# drawbars_v12_2019.net
KiCad netlist of a schematic drawn in EAGLE
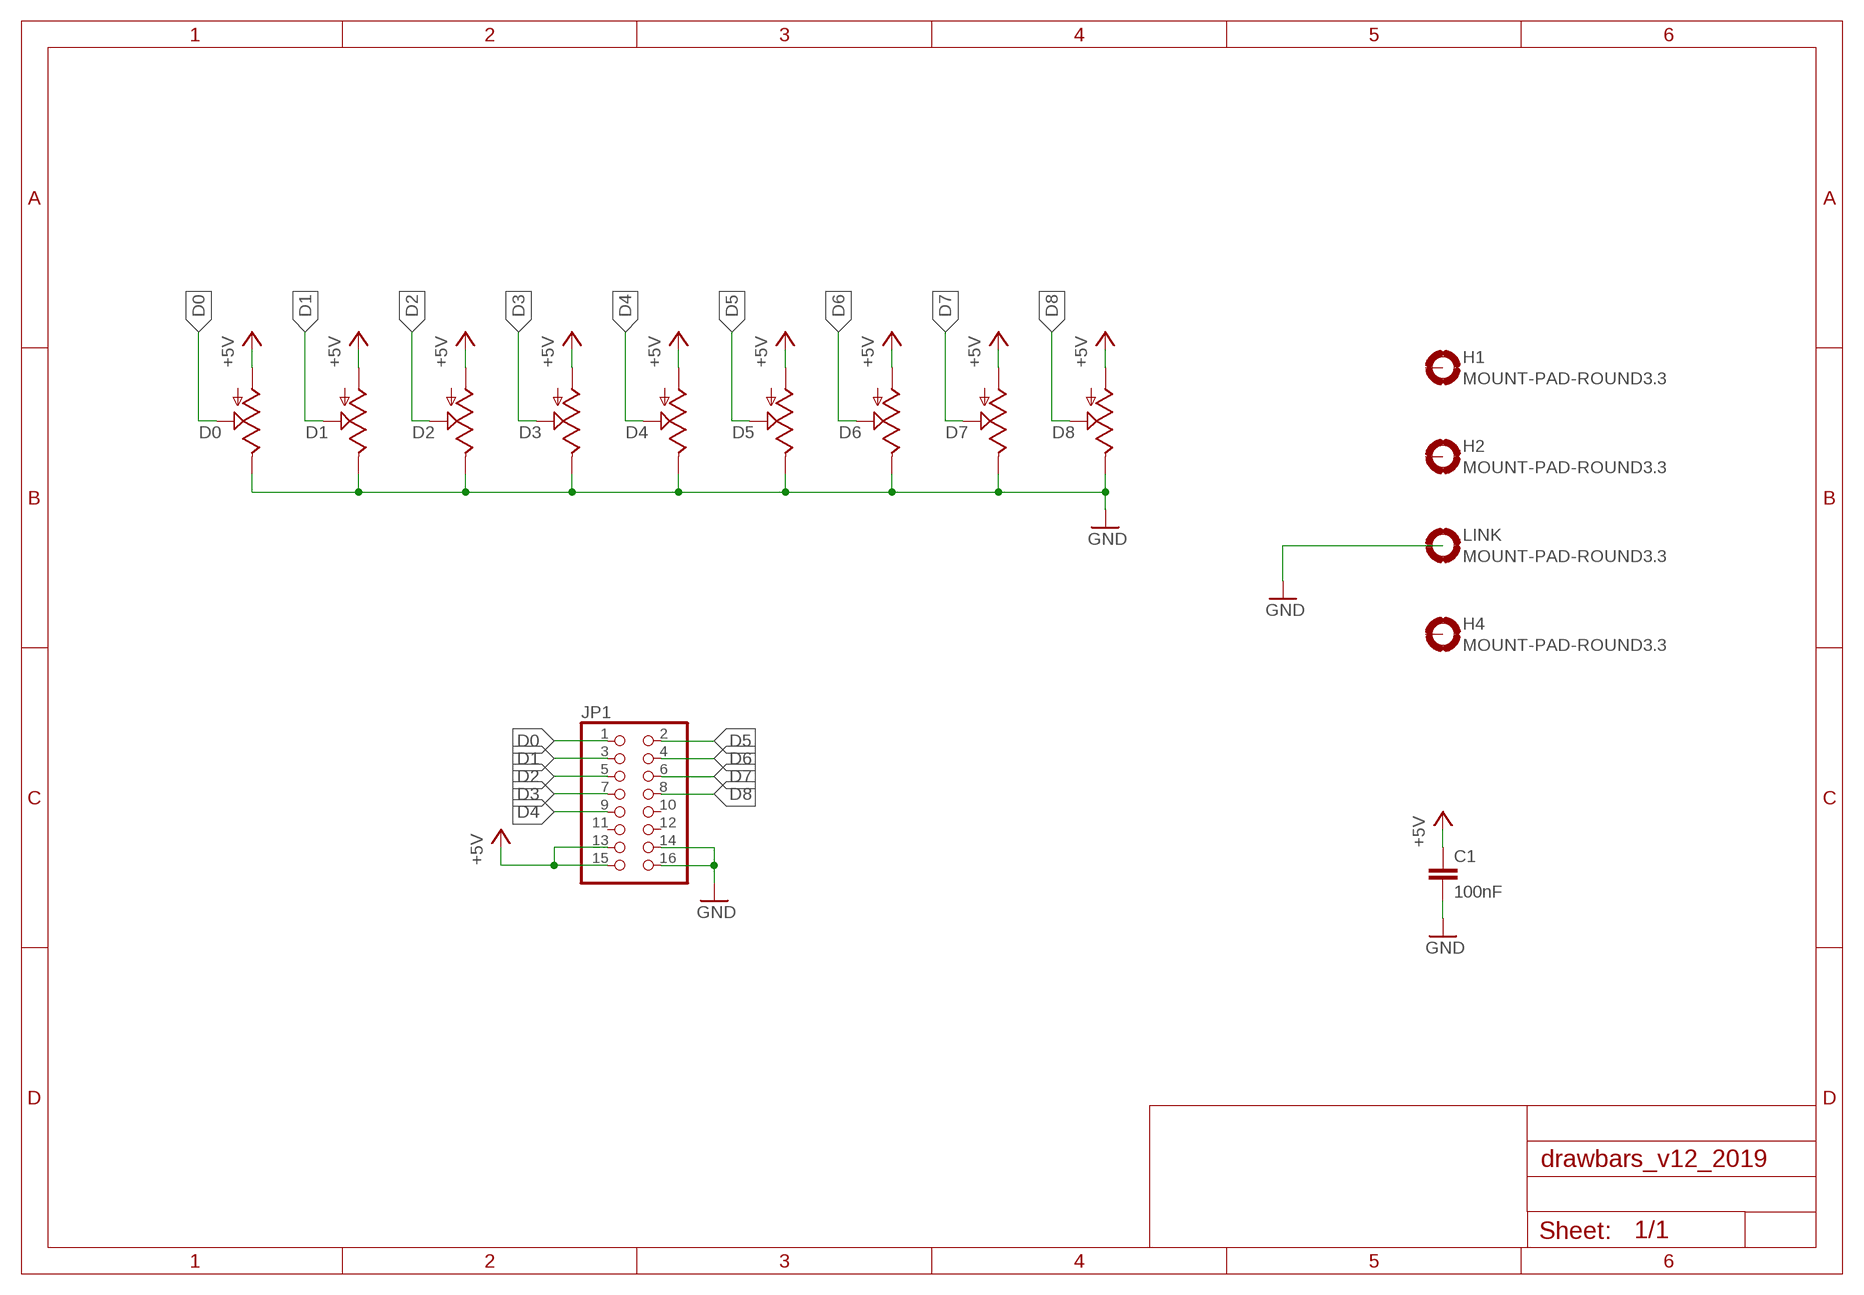
[diagram p0: schematic, sheet 1]

(export (version "E")
  (design (tool "Eeschema 10.0.6"))
  (components
    (comp (ref "C1")
      (value "100nF")
      (footprint "eagle-import:C050-024X044")
      (libsource (lib "eagle-import") (part "C-EU050-024X044"))
    )
    (comp (ref "D0")
      (value "POTENTIOMETER")
      (footprint "eagle-import:ALPHA_DRAWBARS")
      (libsource (lib "eagle-import") (part "POTENTIOMETER"))
    )
    (comp (ref "D1")
      (value "POTENTIOMETER")
      (footprint "eagle-import:ALPHA_DRAWBARS")
      (libsource (lib "eagle-import") (part "POTENTIOMETER"))
    )
    (comp (ref "D2")
      (value "POTENTIOMETER")
      (footprint "eagle-import:ALPHA_DRAWBARS")
      (libsource (lib "eagle-import") (part "POTENTIOMETER"))
    )
    (comp (ref "D3")
      (value "POTENTIOMETER")
      (footprint "eagle-import:ALPHA_DRAWBARS")
      (libsource (lib "eagle-import") (part "POTENTIOMETER"))
    )
    (comp (ref "D4")
      (value "POTENTIOMETER")
      (footprint "eagle-import:ALPHA_DRAWBARS")
      (libsource (lib "eagle-import") (part "POTENTIOMETER"))
    )
    (comp (ref "D5")
      (value "POTENTIOMETER")
      (footprint "eagle-import:ALPHA_DRAWBARS")
      (libsource (lib "eagle-import") (part "POTENTIOMETER"))
    )
    (comp (ref "D6")
      (value "POTENTIOMETER")
      (footprint "eagle-import:ALPHA_DRAWBARS")
      (libsource (lib "eagle-import") (part "POTENTIOMETER"))
    )
    (comp (ref "D7")
      (value "POTENTIOMETER")
      (footprint "eagle-import:ALPHA_DRAWBARS")
      (libsource (lib "eagle-import") (part "POTENTIOMETER"))
    )
    (comp (ref "D8")
      (value "POTENTIOMETER")
      (footprint "eagle-import:ALPHA_DRAWBARS")
      (libsource (lib "eagle-import") (part "POTENTIOMETER"))
    )
    (comp (ref "H1")
      (value "MOUNT-PAD-ROUND3.3")
      (footprint "eagle-import:3,3-PAD")
      (libsource (lib "eagle-import") (part "MOUNT-PAD-ROUND3.3"))
    )
    (comp (ref "H2")
      (value "MOUNT-PAD-ROUND3.3")
      (footprint "eagle-import:3,3-PAD")
      (libsource (lib "eagle-import") (part "MOUNT-PAD-ROUND3.3"))
    )
    (comp (ref "H4")
      (value "MOUNT-PAD-ROUND3.3")
      (footprint "eagle-import:3,3-PAD")
      (libsource (lib "eagle-import") (part "MOUNT-PAD-ROUND3.3"))
    )
    (comp (ref "JP1")
      (value "PINHD-2X8")
      (footprint "eagle-import:2X08")
      (libsource (lib "eagle-import") (part "PINHD-2X8"))
    )
    (comp (ref "LINK")
      (value "MOUNT-PAD-ROUND3.3")
      (footprint "eagle-import:3,3-PAD")
      (libsource (lib "eagle-import") (part "MOUNT-PAD-ROUND3.3"))
    )
  )
  (nets
    (net (code "1") (name "+5V") (class "Default")
      (node (ref "C1") (pin "1") (pinfunction "1_1") (pintype "passive"))
      (node (ref "D0") (pin "P$2") (pinfunction "1_P$2") (pintype "passive"))
      (node (ref "D1") (pin "P$2") (pinfunction "1_P$2") (pintype "passive"))
      (node (ref "D2") (pin "P$2") (pinfunction "1_P$2") (pintype "passive"))
      (node (ref "D3") (pin "P$2") (pinfunction "1_P$2") (pintype "passive"))
      (node (ref "D4") (pin "P$2") (pinfunction "1_P$2") (pintype "passive"))
      (node (ref "D5") (pin "P$2") (pinfunction "1_P$2") (pintype "passive"))
      (node (ref "D6") (pin "P$2") (pinfunction "1_P$2") (pintype "passive"))
      (node (ref "D7") (pin "P$2") (pinfunction "1_P$2") (pintype "passive"))
      (node (ref "D8") (pin "P$2") (pinfunction "1_P$2") (pintype "passive"))
      (node (ref "JP1") (pin "13") (pinfunction "13_13") (pintype "passive"))
      (node (ref "JP1") (pin "15") (pinfunction "15_15") (pintype "passive"))
    )
    (net (code "2") (name "D0") (class "Default")
      (node (ref "D0") (pin "P$3") (pinfunction "2_P$3") (pintype "passive"))
      (node (ref "JP1") (pin "1") (pinfunction "1_1") (pintype "passive"))
    )
    (net (code "3") (name "D1") (class "Default")
      (node (ref "D1") (pin "P$3") (pinfunction "2_P$3") (pintype "passive"))
      (node (ref "JP1") (pin "3") (pinfunction "3_3") (pintype "passive"))
    )
    (net (code "4") (name "D2") (class "Default")
      (node (ref "D2") (pin "P$3") (pinfunction "2_P$3") (pintype "passive"))
      (node (ref "JP1") (pin "5") (pinfunction "5_5") (pintype "passive"))
    )
    (net (code "5") (name "D3") (class "Default")
      (node (ref "D3") (pin "P$3") (pinfunction "2_P$3") (pintype "passive"))
      (node (ref "JP1") (pin "7") (pinfunction "7_7") (pintype "passive"))
    )
    (net (code "6") (name "D4") (class "Default")
      (node (ref "D4") (pin "P$3") (pinfunction "2_P$3") (pintype "passive"))
      (node (ref "JP1") (pin "9") (pinfunction "9_9") (pintype "passive"))
    )
    (net (code "7") (name "D5") (class "Default")
      (node (ref "D5") (pin "P$3") (pinfunction "2_P$3") (pintype "passive"))
      (node (ref "JP1") (pin "2") (pinfunction "2_2") (pintype "passive"))
    )
    (net (code "8") (name "D6") (class "Default")
      (node (ref "D6") (pin "P$3") (pinfunction "2_P$3") (pintype "passive"))
      (node (ref "JP1") (pin "4") (pinfunction "4_4") (pintype "passive"))
    )
    (net (code "9") (name "D7") (class "Default")
      (node (ref "D7") (pin "P$3") (pinfunction "2_P$3") (pintype "passive"))
      (node (ref "JP1") (pin "6") (pinfunction "6_6") (pintype "passive"))
    )
    (net (code "10") (name "D8") (class "Default")
      (node (ref "D8") (pin "P$3") (pinfunction "2_P$3") (pintype "passive"))
      (node (ref "JP1") (pin "8") (pinfunction "8_8") (pintype "passive"))
    )
    (net (code "11") (name "GND") (class "Default")
      (node (ref "C1") (pin "2") (pinfunction "2_2") (pintype "passive"))
      (node (ref "D0") (pin "P$1") (pinfunction "3_P$1") (pintype "passive"))
      (node (ref "D1") (pin "P$1") (pinfunction "3_P$1") (pintype "passive"))
      (node (ref "D2") (pin "P$1") (pinfunction "3_P$1") (pintype "passive"))
      (node (ref "D3") (pin "P$1") (pinfunction "3_P$1") (pintype "passive"))
      (node (ref "D4") (pin "P$1") (pinfunction "3_P$1") (pintype "passive"))
      (node (ref "D5") (pin "P$1") (pinfunction "3_P$1") (pintype "passive"))
      (node (ref "D6") (pin "P$1") (pinfunction "3_P$1") (pintype "passive"))
      (node (ref "D7") (pin "P$1") (pinfunction "3_P$1") (pintype "passive"))
      (node (ref "D8") (pin "P$1") (pinfunction "3_P$1") (pintype "passive"))
      (node (ref "JP1") (pin "14") (pinfunction "14_14") (pintype "passive"))
      (node (ref "JP1") (pin "16") (pinfunction "16_16") (pintype "passive"))
    )
    (net (code "12") (name "unconnected-(H1-MOUNT-PadB3,3)") (class "Default")
      (node (ref "H1") (pin "B3,3") (pinfunction "MOUNT_B3,3") (pintype "passive"))
    )
    (net (code "13") (name "unconnected-(H2-MOUNT-PadB3,3)") (class "Default")
      (node (ref "H2") (pin "B3,3") (pinfunction "MOUNT_B3,3") (pintype "passive"))
    )
    (net (code "14") (name "unconnected-(H4-MOUNT-PadB3,3)") (class "Default")
      (node (ref "H4") (pin "B3,3") (pinfunction "MOUNT_B3,3") (pintype "passive"))
    )
    (net (code "15") (name "unconnected-(JP1-Pad10)") (class "Default")
      (node (ref "JP1") (pin "10") (pinfunction "10_10") (pintype "passive"))
    )
    (net (code "16") (name "unconnected-(JP1-Pad11)") (class "Default")
      (node (ref "JP1") (pin "11") (pinfunction "11_11") (pintype "passive"))
    )
    (net (code "17") (name "unconnected-(JP1-Pad12)") (class "Default")
      (node (ref "JP1") (pin "12") (pinfunction "12_12") (pintype "passive"))
    )
    (net (code "18") (name "unconnected-(LINK-MOUNT-PadB3,3)") (class "Default")
      (node (ref "LINK") (pin "B3,3") (pinfunction "MOUNT_B3,3") (pintype "passive"))
    )
  )
)
